# DSP_ADAU1451.net
KiCad netlist of a schematic drawn in Altium Designer
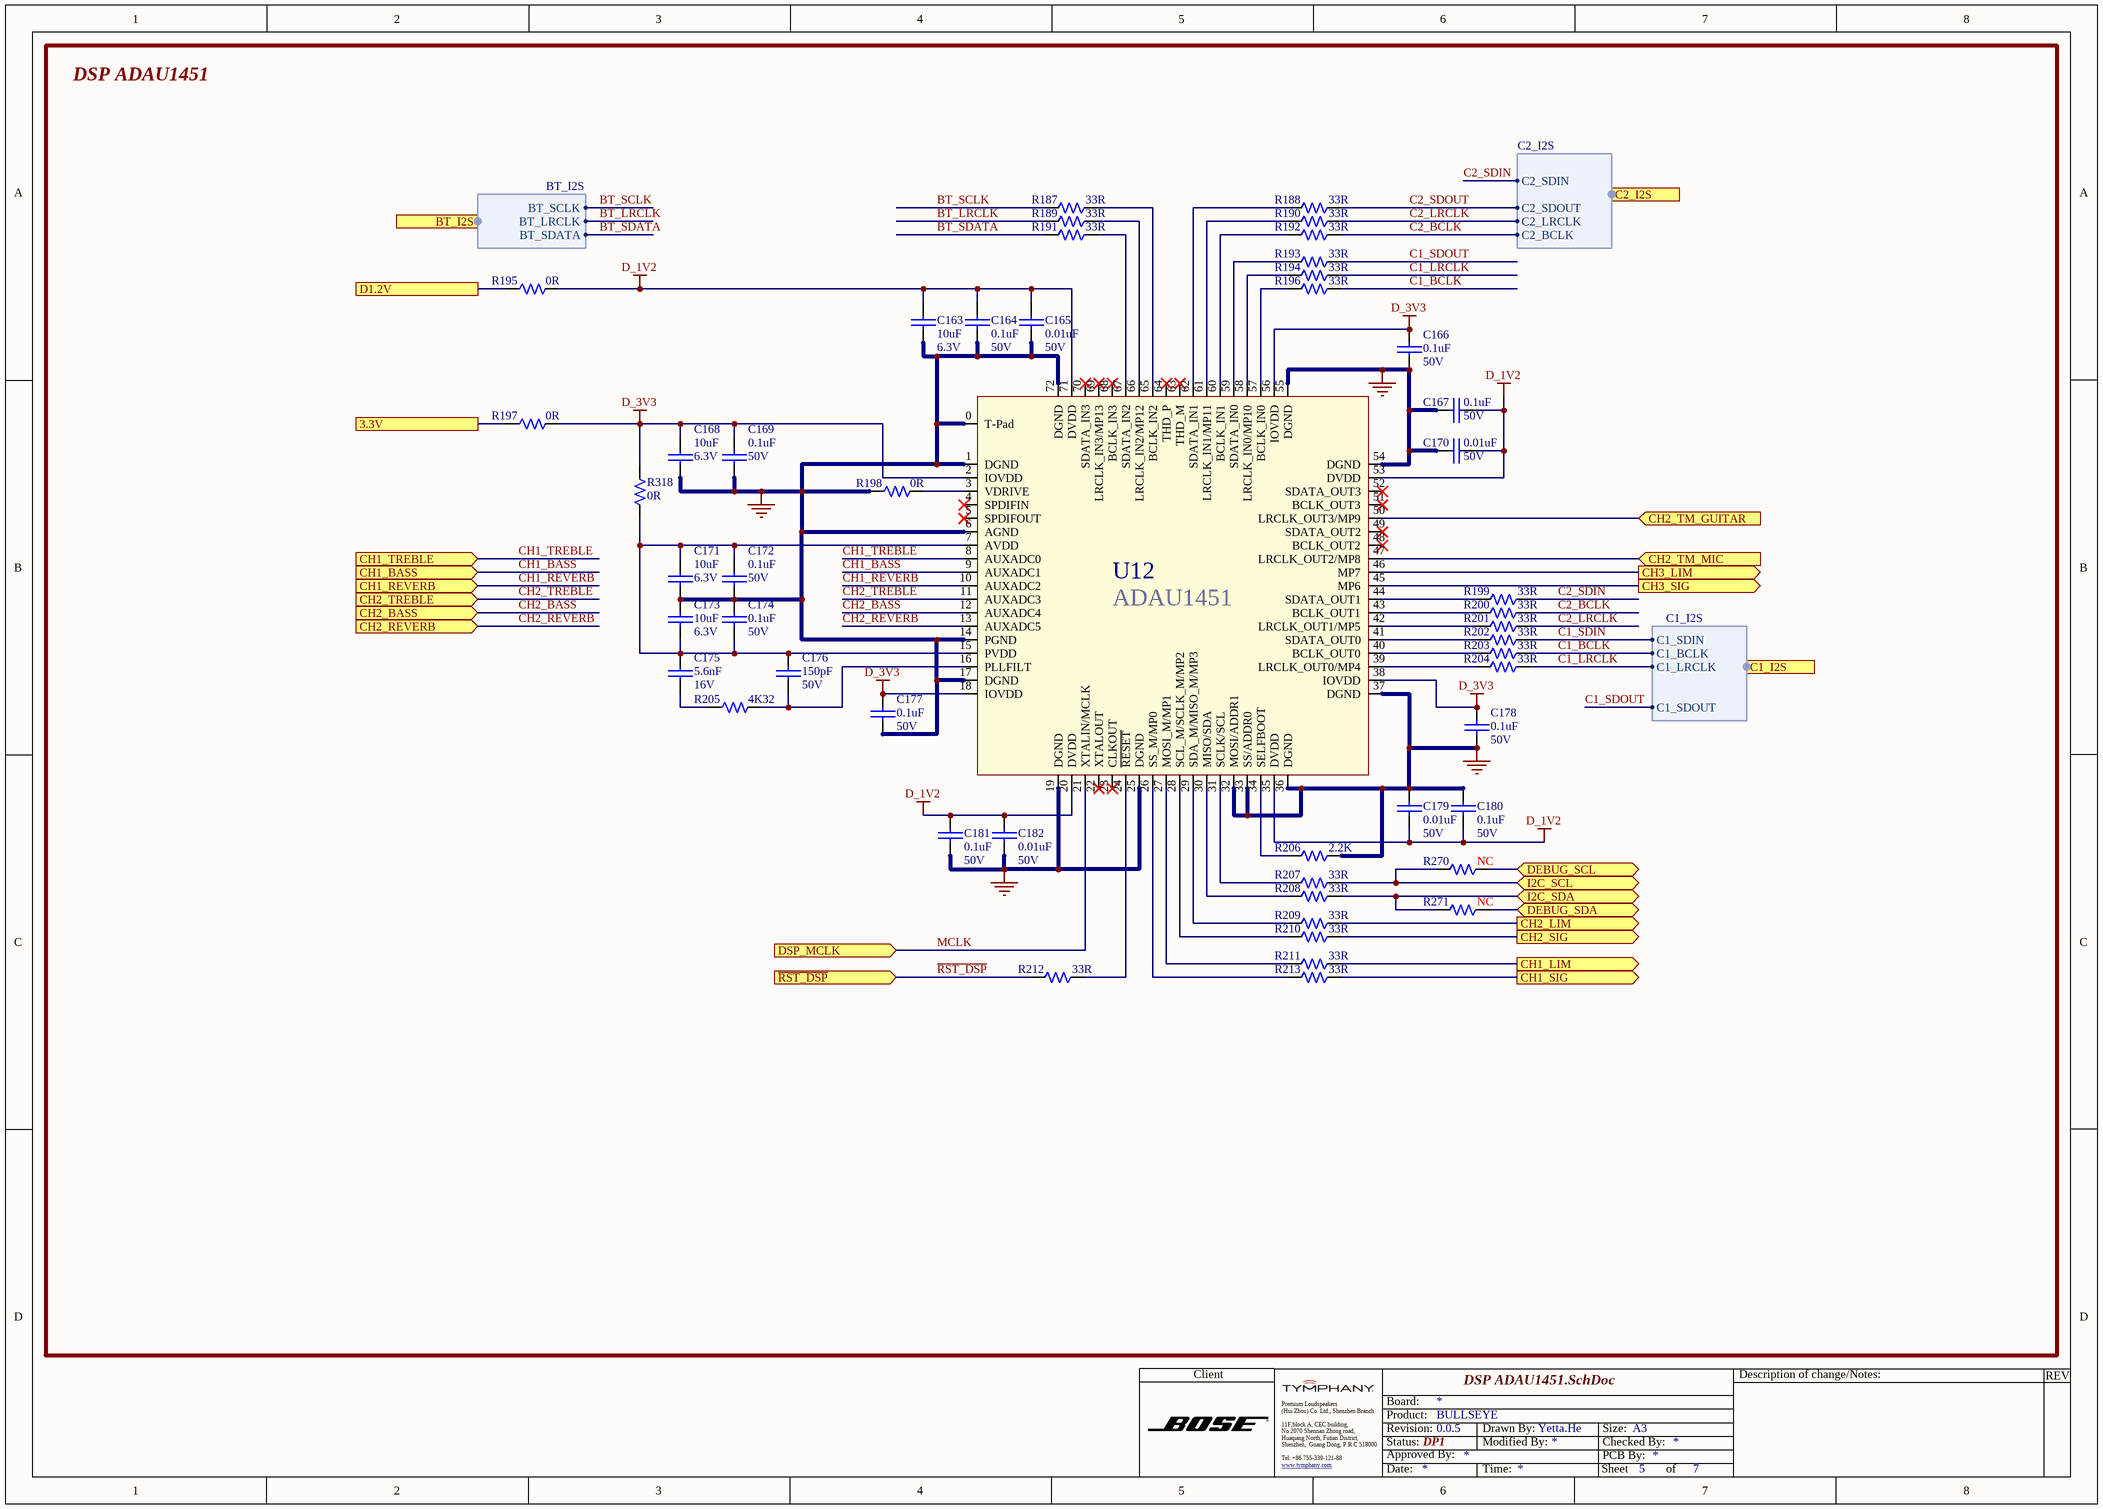
[diagram p0: DSP ADAU1451.SchDoc]

(export (version "E")
  (design (tool "Eeschema 10.0.6"))
  (components
    (comp (ref "C163")
      (value "10uF")
      (footprint "CAPC0603-RW")
      (description "CAP X5R 10UF 6.3V +-10% 0603 SAMSUN L")
      (fields
        (field (name "MFG") "SAMSUNG")
        (field (name "MFG PART") "CL10A106KQ8NNNC")
        (field (name "VOLTAGE") "6.3V")
        (field (name "CREATE_NAME") "Nathan")
      )
      (libsource (lib "P-Capacitors") (part "CAP0603 10uF 6.3V 10%_X5R_SAMSUNG"))
    )
    (comp (ref "C164")
      (value "0.1uF")
      (footprint "CAPC0402-RW")
      (description "CAP X7R .10UF 50V +-10% 0402 WALSIN L")
      (fields
        (field (name "TOLERANCE") "10%")
        (field (name "VOLTAGE") "50V")
        (field (name "Comment") "PWL456470-1040")
        (field (name "CREATE_NAME") "TOM@Deftronics")
      )
      (libsource (lib "P-Capacitors") (part "CAP0402 0.1uF 50V 10%"))
    )
    (comp (ref "C165")
      (value "0.01uF")
      (footprint "CAPC0402-RW")
      (description "CAP, CER, 0.01uF, 10%, 50V, X7R, 0402, RoHS")
      (fields
        (field (name "TOLERANCE") "10%")
        (field (name "VOLTAGE") "50V")
        (field (name "Comment") "PWL456470-1030")
        (field (name "CREATE_NAME") "Evan@Deftronics")
      )
      (libsource (lib "P-Capacitors") (part "CAP0402 0.01uF 50V 10%"))
    )
    (comp (ref "C166")
      (value "0.1uF")
      (footprint "CAPC0402-RW")
      (description "CAP X7R .10UF 50V +-10% 0402 WALSIN L")
      (fields
        (field (name "TOLERANCE") "10%")
        (field (name "VOLTAGE") "50V")
        (field (name "Comment") "PWL456470-1040")
        (field (name "CREATE_NAME") "TOM@Deftronics")
      )
      (libsource (lib "P-Capacitors") (part "CAP0402 0.1uF 50V 10%"))
    )
    (comp (ref "C167")
      (value "0.1uF")
      (footprint "CAPC0402-RW")
      (description "CAP X7R .10UF 50V +-10% 0402 WALSIN L")
      (fields
        (field (name "TOLERANCE") "10%")
        (field (name "VOLTAGE") "50V")
        (field (name "Comment") "PWL456470-1040")
        (field (name "CREATE_NAME") "TOM@Deftronics")
      )
      (libsource (lib "P-Capacitors") (part "CAP0402 0.1uF 50V 10%"))
    )
    (comp (ref "C168")
      (value "10uF")
      (footprint "CAPC0603-RW")
      (description "CAP X5R 10UF 6.3V +-10% 0603 SAMSUN L")
      (fields
        (field (name "MFG") "SAMSUNG")
        (field (name "MFG PART") "CL10A106KQ8NNNC")
        (field (name "VOLTAGE") "6.3V")
        (field (name "CREATE_NAME") "Nathan")
      )
      (libsource (lib "P-Capacitors") (part "CAP0603 10uF 6.3V 10%_X5R_SAMSUNG"))
    )
    (comp (ref "C169")
      (value "0.1uF")
      (footprint "CAPC0402-RW")
      (description "CAP X7R .10UF 50V +-10% 0402 WALSIN L")
      (fields
        (field (name "TOLERANCE") "10%")
        (field (name "VOLTAGE") "50V")
        (field (name "Comment") "PWL456470-1040")
        (field (name "CREATE_NAME") "TOM@Deftronics")
      )
      (libsource (lib "P-Capacitors") (part "CAP0402 0.1uF 50V 10%"))
    )
    (comp (ref "C170")
      (value "0.01uF")
      (footprint "CAPC0402-RW")
      (description "CAP, CER, 0.01uF, 10%, 50V, X7R, 0402, RoHS")
      (fields
        (field (name "TOLERANCE") "10%")
        (field (name "VOLTAGE") "50V")
        (field (name "Comment") "PWL456470-1030")
        (field (name "CREATE_NAME") "Evan@Deftronics")
      )
      (libsource (lib "P-Capacitors") (part "CAP0402 0.01uF 50V 10%"))
    )
    (comp (ref "C171")
      (value "10uF")
      (footprint "CAPC0603-RW")
      (description "CAP X5R 10UF 6.3V +-10% 0603 SAMSUN L")
      (fields
        (field (name "MFG") "SAMSUNG")
        (field (name "MFG PART") "CL10A106KQ8NNNC")
        (field (name "VOLTAGE") "6.3V")
        (field (name "CREATE_NAME") "Nathan")
      )
      (libsource (lib "P-Capacitors") (part "CAP0603 10uF 6.3V 10%_X5R_SAMSUNG"))
    )
    (comp (ref "C172")
      (value "0.1uF")
      (footprint "CAPC0402-RW")
      (description "CAP X7R .10UF 50V +-10% 0402 WALSIN L")
      (fields
        (field (name "TOLERANCE") "10%")
        (field (name "VOLTAGE") "50V")
        (field (name "Comment") "PWL456470-1040")
        (field (name "CREATE_NAME") "TOM@Deftronics")
      )
      (libsource (lib "P-Capacitors") (part "CAP0402 0.1uF 50V 10%"))
    )
    (comp (ref "C173")
      (value "10uF")
      (footprint "CAPC0603-RW")
      (description "CAP X5R 10UF 6.3V +-10% 0603 SAMSUN L")
      (fields
        (field (name "MFG") "SAMSUNG")
        (field (name "MFG PART") "CL10A106KQ8NNNC")
        (field (name "VOLTAGE") "6.3V")
        (field (name "CREATE_NAME") "Nathan")
      )
      (libsource (lib "P-Capacitors") (part "CAP0603 10uF 6.3V 10%_X5R_SAMSUNG"))
    )
    (comp (ref "C174")
      (value "0.1uF")
      (footprint "CAPC0402-RW")
      (description "CAP X7R .10UF 50V +-10% 0402 WALSIN L")
      (fields
        (field (name "TOLERANCE") "10%")
        (field (name "VOLTAGE") "50V")
        (field (name "Comment") "PWL456470-1040")
        (field (name "CREATE_NAME") "TOM@Deftronics")
      )
      (libsource (lib "P-Capacitors") (part "CAP0402 0.1uF 50V 10%"))
    )
    (comp (ref "C175")
      (value "5.6nF")
      (footprint "CAPC0402-RW")
      (description "CHIP CAP 10% 16V 0402 X7R  5.6nF")
      (fields (field (name "MFG") "Walsin") (field (name "TOLERANCE") "10%") (field (name "VOLTAGE") "16V"))
      (libsource (lib "P-Capacitors") (part "CAP0402 5.6nF 16V 10%"))
    )
    (comp (ref "C176")
      (value "150pF")
      (footprint "CAPC0603-RW")
      (description "CAP NPO 150PF 50V +-5% 0603 WALSIN L")
      (fields
        (field (name "MFG") "WALSIN")
        (field (name "TOLERANCE") "5%")
        (field (name "VOLTAGE") "50V")
        (field (name "CREATE_NAME") "Nathan")
      )
      (libsource (lib "P-Capacitors") (part "CAP0603 150pF 50V 5%_NPO_WALSIN"))
    )
    (comp (ref "C177")
      (value "0.1uF")
      (footprint "CAPC0402-RW")
      (description "CAP X7R .10UF 50V +-10% 0402 WALSIN L")
      (fields
        (field (name "TOLERANCE") "10%")
        (field (name "VOLTAGE") "50V")
        (field (name "Comment") "PWL456470-1040")
        (field (name "CREATE_NAME") "TOM@Deftronics")
      )
      (libsource (lib "P-Capacitors") (part "CAP0402 0.1uF 50V 10%"))
    )
    (comp (ref "C178")
      (value "0.1uF")
      (footprint "CAPC0402-RW")
      (description "CAP X7R .10UF 50V +-10% 0402 WALSIN L")
      (fields
        (field (name "TOLERANCE") "10%")
        (field (name "VOLTAGE") "50V")
        (field (name "Comment") "PWL456470-1040")
        (field (name "CREATE_NAME") "TOM@Deftronics")
      )
      (libsource (lib "P-Capacitors") (part "CAP0402 0.1uF 50V 10%"))
    )
    (comp (ref "C179")
      (value "0.01uF")
      (footprint "CAPC0402-RW")
      (description "CAP, CER, 0.01uF, 10%, 50V, X7R, 0402, RoHS")
      (fields
        (field (name "TOLERANCE") "10%")
        (field (name "VOLTAGE") "50V")
        (field (name "Comment") "PWL456470-1030")
        (field (name "CREATE_NAME") "Evan@Deftronics")
      )
      (libsource (lib "P-Capacitors") (part "CAP0402 0.01uF 50V 10%"))
    )
    (comp (ref "C180")
      (value "0.1uF")
      (footprint "CAPC0402-RW")
      (description "CAP X7R .10UF 50V +-10% 0402 WALSIN L")
      (fields
        (field (name "TOLERANCE") "10%")
        (field (name "VOLTAGE") "50V")
        (field (name "Comment") "PWL456470-1040")
        (field (name "CREATE_NAME") "TOM@Deftronics")
      )
      (libsource (lib "P-Capacitors") (part "CAP0402 0.1uF 50V 10%"))
    )
    (comp (ref "C181")
      (value "0.1uF")
      (footprint "CAPC0402-RW")
      (description "CAP X7R .10UF 50V +-10% 0402 WALSIN L")
      (fields
        (field (name "TOLERANCE") "10%")
        (field (name "VOLTAGE") "50V")
        (field (name "Comment") "PWL456470-1040")
        (field (name "CREATE_NAME") "TOM@Deftronics")
      )
      (libsource (lib "P-Capacitors") (part "CAP0402 0.1uF 50V 10%"))
    )
    (comp (ref "C182")
      (value "0.01uF")
      (footprint "CAPC0402-RW")
      (description "CAP, CER, 0.01uF, 10%, 50V, X7R, 0402, RoHS")
      (fields
        (field (name "TOLERANCE") "10%")
        (field (name "VOLTAGE") "50V")
        (field (name "Comment") "PWL456470-1030")
        (field (name "CREATE_NAME") "Evan@Deftronics")
      )
      (libsource (lib "P-Capacitors") (part "CAP0402 0.01uF 50V 10%"))
    )
    (comp (ref "R187")
      (value "33R")
      (footprint "0402-RW")
      (description "CHIP RES 33 OHM 1/16W 1% 0402")
      (fields (field (name "POWER") "1/16W") (field (name "MFG") "WALSIN"))
      (libsource (lib "Q-Resistors") (part "RES0402 1/16W 1% 33 OHM"))
    )
    (comp (ref "R188")
      (value "33R")
      (footprint "0402-RW")
      (description "CHIP RES 33 OHM 1/16W 1% 0402")
      (fields (field (name "POWER") "1/16W") (field (name "MFG") "WALSIN"))
      (libsource (lib "Q-Resistors") (part "RES0402 1/16W 1% 33 OHM"))
    )
    (comp (ref "R189")
      (value "33R")
      (footprint "0402-RW")
      (description "CHIP RES 33 OHM 1/16W 1% 0402")
      (fields (field (name "POWER") "1/16W") (field (name "MFG") "WALSIN"))
      (libsource (lib "Q-Resistors") (part "RES0402 1/16W 1% 33 OHM"))
    )
    (comp (ref "R190")
      (value "33R")
      (footprint "0402-RW")
      (description "CHIP RES 33 OHM 1/16W 1% 0402")
      (fields (field (name "POWER") "1/16W") (field (name "MFG") "WALSIN"))
      (libsource (lib "Q-Resistors") (part "RES0402 1/16W 1% 33 OHM"))
    )
    (comp (ref "R191")
      (value "33R")
      (footprint "0402-RW")
      (description "CHIP RES 33 OHM 1/16W 1% 0402")
      (fields (field (name "POWER") "1/16W") (field (name "MFG") "WALSIN"))
      (libsource (lib "Q-Resistors") (part "RES0402 1/16W 1% 33 OHM"))
    )
    (comp (ref "R192")
      (value "33R")
      (footprint "0402-RW")
      (description "CHIP RES 33 OHM 1/16W 1% 0402")
      (fields (field (name "POWER") "1/16W") (field (name "MFG") "WALSIN"))
      (libsource (lib "Q-Resistors") (part "RES0402 1/16W 1% 33 OHM"))
    )
    (comp (ref "R193")
      (value "33R")
      (footprint "0402-RW")
      (description "CHIP RES 33 OHM 1/16W 1% 0402")
      (fields (field (name "POWER") "1/16W") (field (name "MFG") "WALSIN"))
      (libsource (lib "Q-Resistors") (part "RES0402 1/16W 1% 33 OHM"))
    )
    (comp (ref "R194")
      (value "33R")
      (footprint "0402-RW")
      (description "CHIP RES 33 OHM 1/16W 1% 0402")
      (fields (field (name "POWER") "1/16W") (field (name "MFG") "WALSIN"))
      (libsource (lib "Q-Resistors") (part "RES0402 1/16W 1% 33 OHM"))
    )
    (comp (ref "R195")
      (value "0R")
      (footprint "0603-RW")
      (description "CHIP 0 OHM 0 OHM 0 OHM 0603 WALSIN L")
      (fields (field (name "POWER") "1/10W") (field (name "MFG PART") "WR06X000PTL"))
      (libsource (lib "Q-Resistors") (part "RES0603 1/10W 0 OHM_WALSIN"))
    )
    (comp (ref "R196")
      (value "33R")
      (footprint "0402-RW")
      (description "CHIP RES 33 OHM 1/16W 1% 0402")
      (fields (field (name "POWER") "1/16W") (field (name "MFG") "WALSIN"))
      (libsource (lib "Q-Resistors") (part "RES0402 1/16W 1% 33 OHM"))
    )
    (comp (ref "R197")
      (value "0R")
      (footprint "0603-RW")
      (description "CHIP 0 OHM 0 OHM 0 OHM 0603 WALSIN L")
      (fields (field (name "POWER") "1/10W") (field (name "MFG PART") "WR06X000PTL"))
      (libsource (lib "Q-Resistors") (part "RES0603 1/10W 0 OHM_WALSIN"))
    )
    (comp (ref "R198")
      (value "0R")
      (footprint "0603-RW")
      (description "CHIP 0 OHM 0 OHM 0 OHM 0603 WALSIN L")
      (fields (field (name "POWER") "1/10W") (field (name "MFG PART") "WR06X000PTL"))
      (libsource (lib "Q-Resistors") (part "RES0603 1/10W 0 OHM_WALSIN"))
    )
    (comp (ref "R199")
      (value "33R")
      (footprint "0402-RW")
      (description "CHIP RES 33 OHM 1/16W 1% 0402")
      (fields (field (name "POWER") "1/16W") (field (name "MFG") "WALSIN"))
      (libsource (lib "Q-Resistors") (part "RES0402 1/16W 1% 33 OHM"))
    )
    (comp (ref "R200")
      (value "33R")
      (footprint "0402-RW")
      (description "CHIP RES 33 OHM 1/16W 1% 0402")
      (fields (field (name "POWER") "1/16W") (field (name "MFG") "WALSIN"))
      (libsource (lib "Q-Resistors") (part "RES0402 1/16W 1% 33 OHM"))
    )
    (comp (ref "R201")
      (value "33R")
      (footprint "0402-RW")
      (description "CHIP RES 33 OHM 1/16W 1% 0402")
      (fields (field (name "POWER") "1/16W") (field (name "MFG") "WALSIN"))
      (libsource (lib "Q-Resistors") (part "RES0402 1/16W 1% 33 OHM"))
    )
    (comp (ref "R202")
      (value "33R")
      (footprint "0402-RW")
      (description "CHIP RES 33 OHM 1/16W 1% 0402")
      (fields (field (name "POWER") "1/16W") (field (name "MFG") "WALSIN"))
      (libsource (lib "Q-Resistors") (part "RES0402 1/16W 1% 33 OHM"))
    )
    (comp (ref "R203")
      (value "33R")
      (footprint "0402-RW")
      (description "CHIP RES 33 OHM 1/16W 1% 0402")
      (fields (field (name "POWER") "1/16W") (field (name "MFG") "WALSIN"))
      (libsource (lib "Q-Resistors") (part "RES0402 1/16W 1% 33 OHM"))
    )
    (comp (ref "R204")
      (value "33R")
      (footprint "0402-RW")
      (description "CHIP RES 33 OHM 1/16W 1% 0402")
      (fields (field (name "POWER") "1/16W") (field (name "MFG") "WALSIN"))
      (libsource (lib "Q-Resistors") (part "RES0402 1/16W 1% 33 OHM"))
    )
    (comp (ref "R205")
      (value "4K32")
      (footprint "0402-RW")
      (description "CHIP 4.32K OHM 100PPM +-1% 0402 WALS L")
      (fields
        (field (name "MFG") "WALSIN (華新)")
        (field (name "POWER") "1/16W")
        (field (name "CREATE_NAME") "Nathan")
      )
      (libsource (lib "Q-Resistors") (part "RES0402 1/16W 1% 4.32K OMH_WALSIN"))
    )
    (comp (ref "R206")
      (value "2.2K")
      (footprint "0603-RW")
      (description "GP CHIP RES. 2.2K OHM 1/10W 1% 0603")
      (fields (field (name "POWER") "1/10W") (field (name "Comment") "QCF011030-2201"))
      (libsource (lib "Q-Resistors") (part "RES0603 1/10W 1% 2.2K OHM"))
    )
    (comp (ref "R207")
      (value "33R")
      (footprint "0402-RW")
      (description "CHIP RES 33 OHM 1/16W 1% 0402")
      (fields (field (name "POWER") "1/16W") (field (name "MFG") "WALSIN"))
      (libsource (lib "Q-Resistors") (part "RES0402 1/16W 1% 33 OHM"))
    )
    (comp (ref "R208")
      (value "33R")
      (footprint "0402-RW")
      (description "CHIP RES 33 OHM 1/16W 1% 0402")
      (fields (field (name "POWER") "1/16W") (field (name "MFG") "WALSIN"))
      (libsource (lib "Q-Resistors") (part "RES0402 1/16W 1% 33 OHM"))
    )
    (comp (ref "R209")
      (value "33R")
      (footprint "0402-RW")
      (description "CHIP RES 33 OHM 1/16W 1% 0402")
      (fields (field (name "POWER") "1/16W") (field (name "MFG") "WALSIN"))
      (libsource (lib "Q-Resistors") (part "RES0402 1/16W 1% 33 OHM"))
    )
    (comp (ref "R210")
      (value "33R")
      (footprint "0402-RW")
      (description "CHIP RES 33 OHM 1/16W 1% 0402")
      (fields (field (name "POWER") "1/16W") (field (name "MFG") "WALSIN"))
      (libsource (lib "Q-Resistors") (part "RES0402 1/16W 1% 33 OHM"))
    )
    (comp (ref "R211")
      (value "33R")
      (footprint "0402-RW")
      (description "CHIP RES 33 OHM 1/16W 1% 0402")
      (fields (field (name "POWER") "1/16W") (field (name "MFG") "WALSIN"))
      (libsource (lib "Q-Resistors") (part "RES0402 1/16W 1% 33 OHM"))
    )
    (comp (ref "R212")
      (value "33R")
      (footprint "0402-RW")
      (description "CHIP RES 33 OHM 1/16W 1% 0402")
      (fields (field (name "POWER") "1/16W") (field (name "MFG") "WALSIN"))
      (libsource (lib "Q-Resistors") (part "RES0402 1/16W 1% 33 OHM"))
    )
    (comp (ref "R213")
      (value "33R")
      (footprint "0402-RW")
      (description "CHIP RES 33 OHM 1/16W 1% 0402")
      (fields (field (name "POWER") "1/16W") (field (name "MFG") "WALSIN"))
      (libsource (lib "Q-Resistors") (part "RES0402 1/16W 1% 33 OHM"))
    )
    (comp (ref "R270")
      (value "NC")
      (footprint "0603-RW")
      (fields (field (name "Comment") "RES0603 NC") (field (name "CREATE_NAME") "Tom"))
      (libsource (lib "Temporary") (part "RES0603 NC"))
    )
    (comp (ref "R271")
      (value "NC")
      (footprint "0603-RW")
      (fields (field (name "Comment") "RES0603 NC") (field (name "CREATE_NAME") "Tom"))
      (libsource (lib "Temporary") (part "RES0603 NC"))
    )
    (comp (ref "R318")
      (value "0R")
      (footprint "0603-RW")
      (description "CHIP 0 OHM 0 OHM 0 OHM 0603 WALSIN L")
      (fields (field (name "POWER") "1/10W") (field (name "MFG PART") "WR06X000PTL"))
      (libsource (lib "Q-Resistors") (part "RES0603 1/10W 0 OHM_WALSIN"))
    )
    (comp (ref "U12")
      (value "T610000050936")
      (footprint "QFN50P1000X1000X100-72N")
      (description "SP ADAU1451 LFCSP-72 ADI (AN K")
      (fields
        (field (name "MFG") "ADI (ANALOG DEVICES)")
        (field (name "MFG PART") "ADAU1451")
        (field (name "CREATE_NAME") "Tom")
      )
      (libsource (lib "R-Semiconductors") (part "ADAU1451"))
    )
  )
  (nets
    (net (code "4") (name "/3.3V") (class "Default")
      (node (ref "R197") (pin "1") (pinfunction "1_1") (pintype "passive"))
    )
    (net (code "5") (name "/BT_LRCLK") (class "Default")
      (node (ref "R189") (pin "2") (pinfunction "2_2") (pintype "passive"))
    )
    (net (code "6") (name "/BT_SCLK") (class "Default")
      (node (ref "R187") (pin "2") (pinfunction "2_2") (pintype "passive"))
    )
    (net (code "7") (name "/BT_SDATA") (class "Default")
      (node (ref "R191") (pin "2") (pinfunction "2_2") (pintype "passive"))
    )
    (net (code "8") (name "/C1_BCLK") (class "Default")
      (node (ref "R196") (pin "1") (pinfunction "1_1") (pintype "passive"))
      (node (ref "R203") (pin "1") (pinfunction "1_1") (pintype "passive"))
    )
    (net (code "9") (name "/C1_LRCLK") (class "Default")
      (node (ref "R194") (pin "1") (pinfunction "1_1") (pintype "passive"))
      (node (ref "R204") (pin "1") (pinfunction "1_1") (pintype "passive"))
    )
    (net (code "10") (name "/C1_SDIN") (class "Default")
      (node (ref "R202") (pin "1") (pinfunction "1_1") (pintype "passive"))
    )
    (net (code "11") (name "/C1_SDOUT") (class "Default")
      (node (ref "R193") (pin "1") (pinfunction "1_1") (pintype "passive"))
    )
    (net (code "12") (name "/C2_BCLK") (class "Default")
      (node (ref "R192") (pin "1") (pinfunction "1_1") (pintype "passive"))
      (node (ref "R200") (pin "1") (pinfunction "1_1") (pintype "passive"))
    )
    (net (code "13") (name "/C2_LRCLK") (class "Default")
      (node (ref "R190") (pin "1") (pinfunction "1_1") (pintype "passive"))
      (node (ref "R201") (pin "1") (pinfunction "1_1") (pintype "passive"))
    )
    (net (code "14") (name "/C2_SDIN") (class "Default")
      (node (ref "R199") (pin "1") (pinfunction "1_1") (pintype "passive"))
    )
    (net (code "15") (name "/C2_SDOUT") (class "Default")
      (node (ref "R188") (pin "1") (pinfunction "1_1") (pintype "passive"))
    )
    (net (code "16") (name "/CH1_BASS") (class "Default")
      (node (ref "U12") (pin "9") (pinfunction "AUXADC1_9") (pintype "passive"))
    )
    (net (code "17") (name "/CH1_LIM") (class "Default")
      (node (ref "R211") (pin "1") (pinfunction "1_1") (pintype "passive"))
    )
    (net (code "18") (name "/CH1_REVERB") (class "Default")
      (node (ref "U12") (pin "10") (pinfunction "AUXADC2_10") (pintype "passive"))
    )
    (net (code "19") (name "/CH1_SIG") (class "Default")
      (node (ref "R213") (pin "1") (pinfunction "1_1") (pintype "passive"))
    )
    (net (code "20") (name "/CH1_TREBLE") (class "Default")
      (node (ref "U12") (pin "8") (pinfunction "AUXADC0_8") (pintype "passive"))
    )
    (net (code "21") (name "/CH2_BASS") (class "Default")
      (node (ref "U12") (pin "12") (pinfunction "AUXADC4_12") (pintype "passive"))
    )
    (net (code "22") (name "/CH2_LIM") (class "Default")
      (node (ref "R209") (pin "1") (pinfunction "1_1") (pintype "passive"))
    )
    (net (code "23") (name "/CH2_REVERB") (class "Default")
      (node (ref "U12") (pin "13") (pinfunction "AUXADC5_13") (pintype "passive"))
    )
    (net (code "24") (name "/CH2_SIG") (class "Default")
      (node (ref "R210") (pin "1") (pinfunction "1_1") (pintype "passive"))
    )
    (net (code "25") (name "/CH2_TM_GUITAR") (class "Default")
      (node (ref "U12") (pin "50") (pinfunction "LRCLK_OUT3/MP9_50") (pintype "passive"))
    )
    (net (code "26") (name "/CH2_TM_MIC") (class "Default")
      (node (ref "U12") (pin "47") (pinfunction "LRCLK_OUT2/MP8_47") (pintype "passive"))
    )
    (net (code "27") (name "/CH2_TREBLE") (class "Default")
      (node (ref "U12") (pin "11") (pinfunction "AUXADC3_11") (pintype "passive"))
    )
    (net (code "28") (name "/CH3_LIM") (class "Default")
      (node (ref "U12") (pin "46") (pinfunction "MP7_46") (pintype "passive"))
    )
    (net (code "29") (name "/CH3_SIG") (class "Default")
      (node (ref "U12") (pin "45") (pinfunction "MP6_45") (pintype "passive"))
    )
    (net (code "30") (name "/D1.2V") (class "Default")
      (node (ref "R195") (pin "1") (pinfunction "1_1") (pintype "passive"))
    )
    (net (code "31") (name "/DEBUG_SCL") (class "Default")
      (node (ref "R270") (pin "1") (pinfunction "1_1") (pintype "passive"))
    )
    (net (code "32") (name "/DEBUG_SDA") (class "Default")
      (node (ref "R271") (pin "1") (pinfunction "1_1") (pintype "passive"))
    )
    (net (code "33") (name "/I2C_SCL") (class "Default")
      (node (ref "R207") (pin "1") (pinfunction "1_1") (pintype "passive"))
      (node (ref "R270") (pin "2") (pinfunction "2_2") (pintype "passive"))
    )
    (net (code "34") (name "/I2C_SDA") (class "Default")
      (node (ref "R208") (pin "1") (pinfunction "1_1") (pintype "passive"))
      (node (ref "R271") (pin "2") (pinfunction "2_2") (pintype "passive"))
    )
    (net (code "35") (name "/MCLK") (class "Default")
      (node (ref "U12") (pin "21") (pinfunction "XTALIN/MCLK_21") (pintype "passive"))
    )
    (net (code "39") (name "/~{RST_DSP}") (class "Default")
      (node (ref "R212") (pin "2") (pinfunction "2_2") (pintype "passive"))
    )
    (net (code "40") (name "D_1V2") (class "Default")
      (node (ref "C163") (pin "1") (pinfunction "1_1") (pintype "passive"))
      (node (ref "C164") (pin "1") (pinfunction "1_1") (pintype "passive"))
      (node (ref "C165") (pin "1") (pinfunction "1_1") (pintype "passive"))
      (node (ref "C167") (pin "2") (pinfunction "2_2") (pintype "passive"))
      (node (ref "C170") (pin "2") (pinfunction "2_2") (pintype "passive"))
      (node (ref "C179") (pin "2") (pinfunction "2_2") (pintype "passive"))
      (node (ref "C180") (pin "2") (pinfunction "2_2") (pintype "passive"))
      (node (ref "C181") (pin "1") (pinfunction "1_1") (pintype "passive"))
      (node (ref "C182") (pin "1") (pinfunction "1_1") (pintype "passive"))
      (node (ref "R195") (pin "2") (pinfunction "2_2") (pintype "passive"))
      (node (ref "U12") (pin "20") (pinfunction "DVDD_20") (pintype "passive"))
      (node (ref "U12") (pin "35") (pinfunction "DVDD_35") (pintype "passive"))
      (node (ref "U12") (pin "53") (pinfunction "DVDD_53") (pintype "passive"))
      (node (ref "U12") (pin "71") (pinfunction "DVDD_71") (pintype "passive"))
    )
    (net (code "41") (name "D_3V3") (class "Default")
      (node (ref "C166") (pin "1") (pinfunction "1_1") (pintype "passive"))
      (node (ref "C168") (pin "1") (pinfunction "1_1") (pintype "passive"))
      (node (ref "C169") (pin "1") (pinfunction "1_1") (pintype "passive"))
      (node (ref "C177") (pin "1") (pinfunction "1_1") (pintype "passive"))
      (node (ref "C178") (pin "1") (pinfunction "1_1") (pintype "passive"))
      (node (ref "R197") (pin "2") (pinfunction "2_2") (pintype "passive"))
      (node (ref "R318") (pin "1") (pinfunction "1_1") (pintype "passive"))
      (node (ref "U12") (pin "18") (pinfunction "IOVDD_18") (pintype "passive"))
      (node (ref "U12") (pin "2") (pinfunction "IOVDD_2") (pintype "passive"))
      (node (ref "U12") (pin "38") (pinfunction "IOVDD_38") (pintype "passive"))
      (node (ref "U12") (pin "56") (pinfunction "IOVDD_56") (pintype "passive"))
    )
    (net (code "42") (name "GND") (class "Default")
      (node (ref "C163") (pin "2") (pinfunction "2_2") (pintype "passive"))
      (node (ref "C164") (pin "2") (pinfunction "2_2") (pintype "passive"))
      (node (ref "C165") (pin "2") (pinfunction "2_2") (pintype "passive"))
      (node (ref "C166") (pin "2") (pinfunction "2_2") (pintype "passive"))
      (node (ref "C167") (pin "1") (pinfunction "1_1") (pintype "passive"))
      (node (ref "C168") (pin "2") (pinfunction "2_2") (pintype "passive"))
      (node (ref "C169") (pin "2") (pinfunction "2_2") (pintype "passive"))
      (node (ref "C170") (pin "1") (pinfunction "1_1") (pintype "passive"))
      (node (ref "C171") (pin "2") (pinfunction "2_2") (pintype "passive"))
      (node (ref "C172") (pin "2") (pinfunction "2_2") (pintype "passive"))
      (node (ref "C173") (pin "1") (pinfunction "1_1") (pintype "passive"))
      (node (ref "C174") (pin "1") (pinfunction "1_1") (pintype "passive"))
      (node (ref "C177") (pin "2") (pinfunction "2_2") (pintype "passive"))
      (node (ref "C178") (pin "2") (pinfunction "2_2") (pintype "passive"))
      (node (ref "C179") (pin "1") (pinfunction "1_1") (pintype "passive"))
      (node (ref "C180") (pin "1") (pinfunction "1_1") (pintype "passive"))
      (node (ref "C181") (pin "2") (pinfunction "2_2") (pintype "passive"))
      (node (ref "C182") (pin "2") (pinfunction "2_2") (pintype "passive"))
      (node (ref "R198") (pin "1") (pinfunction "1_1") (pintype "passive"))
      (node (ref "R206") (pin "1") (pinfunction "1_1") (pintype "passive"))
      (node (ref "U12") (pin "0") (pinfunction "T-Pad_0") (pintype "passive"))
      (node (ref "U12") (pin "1") (pinfunction "DGND_1") (pintype "passive"))
      (node (ref "U12") (pin "14") (pinfunction "PGND_14") (pintype "passive"))
      (node (ref "U12") (pin "17") (pinfunction "DGND_17") (pintype "passive"))
      (node (ref "U12") (pin "19") (pinfunction "DGND_19") (pintype "passive"))
      (node (ref "U12") (pin "25") (pinfunction "DGND_25") (pintype "passive"))
      (node (ref "U12") (pin "32") (pinfunction "MOSI/ADDR1_32") (pintype "passive"))
      (node (ref "U12") (pin "33") (pinfunction "SS/ADDR0_33") (pintype "passive"))
      (node (ref "U12") (pin "36") (pinfunction "DGND_36") (pintype "passive"))
      (node (ref "U12") (pin "37") (pinfunction "DGND_37") (pintype "passive"))
      (node (ref "U12") (pin "54") (pinfunction "DGND_54") (pintype "passive"))
      (node (ref "U12") (pin "55") (pinfunction "DGND_55") (pintype "passive"))
      (node (ref "U12") (pin "6") (pinfunction "AGND_6") (pintype "passive"))
      (node (ref "U12") (pin "72") (pinfunction "DGND_72") (pintype "passive"))
    )
    (net (code "43") (name "Net-(C175-Pad2)") (class "Default")
      (node (ref "C175") (pin "2") (pinfunction "2_2") (pintype "passive"))
      (node (ref "R205") (pin "1") (pinfunction "1_1") (pintype "passive"))
    )
    (net (code "44") (name "Net-(U12-AVDD)") (class "Default")
      (node (ref "C171") (pin "1") (pinfunction "1_1") (pintype "passive"))
      (node (ref "C172") (pin "1") (pinfunction "1_1") (pintype "passive"))
      (node (ref "C173") (pin "2") (pinfunction "2_2") (pintype "passive"))
      (node (ref "C174") (pin "2") (pinfunction "2_2") (pintype "passive"))
      (node (ref "C175") (pin "1") (pinfunction "1_1") (pintype "passive"))
      (node (ref "C176") (pin "1") (pinfunction "1_1") (pintype "passive"))
      (node (ref "R318") (pin "2") (pinfunction "2_2") (pintype "passive"))
      (node (ref "U12") (pin "15") (pinfunction "PVDD_15") (pintype "passive"))
      (node (ref "U12") (pin "7") (pinfunction "AVDD_7") (pintype "passive"))
    )
    (net (code "45") (name "Net-(U12-BCLK_IN0)") (class "Default")
      (node (ref "R196") (pin "2") (pinfunction "2_2") (pintype "passive"))
      (node (ref "U12") (pin "57") (pinfunction "BCLK_IN0_57") (pintype "passive"))
    )
    (net (code "46") (name "Net-(U12-BCLK_IN1)") (class "Default")
      (node (ref "R192") (pin "2") (pinfunction "2_2") (pintype "passive"))
      (node (ref "U12") (pin "60") (pinfunction "BCLK_IN1_60") (pintype "passive"))
    )
    (net (code "47") (name "Net-(U12-BCLK_IN2)") (class "Default")
      (node (ref "R187") (pin "1") (pinfunction "1_1") (pintype "passive"))
      (node (ref "U12") (pin "65") (pinfunction "BCLK_IN2_65") (pintype "passive"))
    )
    (net (code "48") (name "Net-(U12-BCLK_OUT0)") (class "Default")
      (node (ref "R203") (pin "2") (pinfunction "2_2") (pintype "passive"))
      (node (ref "U12") (pin "40") (pinfunction "BCLK_OUT0_40") (pintype "passive"))
    )
    (net (code "49") (name "Net-(U12-BCLK_OUT1)") (class "Default")
      (node (ref "R200") (pin "2") (pinfunction "2_2") (pintype "passive"))
      (node (ref "U12") (pin "43") (pinfunction "BCLK_OUT1_43") (pintype "passive"))
    )
    (net (code "50") (name "Net-(U12-LRCLK_IN0{slash}MP10)") (class "Default")
      (node (ref "R194") (pin "2") (pinfunction "2_2") (pintype "passive"))
      (node (ref "U12") (pin "58") (pinfunction "LRCLK_IN0/MP10_58") (pintype "passive"))
    )
    (net (code "51") (name "Net-(U12-LRCLK_IN1{slash}MP11)") (class "Default")
      (node (ref "R190") (pin "2") (pinfunction "2_2") (pintype "passive"))
      (node (ref "U12") (pin "61") (pinfunction "LRCLK_IN1/MP11_61") (pintype "passive"))
    )
    (net (code "52") (name "Net-(U12-LRCLK_IN2{slash}MP12)") (class "Default")
      (node (ref "R189") (pin "1") (pinfunction "1_1") (pintype "passive"))
      (node (ref "U12") (pin "66") (pinfunction "LRCLK_IN2/MP12_66") (pintype "passive"))
    )
    (net (code "53") (name "Net-(U12-LRCLK_OUT0{slash}MP4)") (class "Default")
      (node (ref "R204") (pin "2") (pinfunction "2_2") (pintype "passive"))
      (node (ref "U12") (pin "39") (pinfunction "LRCLK_OUT0/MP4_39") (pintype "passive"))
    )
    (net (code "54") (name "Net-(U12-LRCLK_OUT1{slash}MP5)") (class "Default")
      (node (ref "R201") (pin "2") (pinfunction "2_2") (pintype "passive"))
      (node (ref "U12") (pin "42") (pinfunction "LRCLK_OUT1/MP5_42") (pintype "passive"))
    )
    (net (code "55") (name "Net-(U12-MISO{slash}SDA)") (class "Default")
      (node (ref "R208") (pin "2") (pinfunction "2_2") (pintype "passive"))
      (node (ref "U12") (pin "30") (pinfunction "MISO/SDA_30") (pintype "passive"))
    )
    (net (code "56") (name "Net-(U12-MOSI_M{slash}MP1)") (class "Default")
      (node (ref "R211") (pin "2") (pinfunction "2_2") (pintype "passive"))
      (node (ref "U12") (pin "27") (pinfunction "MOSI_M/MP1_27") (pintype "passive"))
    )
    (net (code "57") (name "Net-(U12-PLLFILT)") (class "Default")
      (node (ref "C176") (pin "2") (pinfunction "2_2") (pintype "passive"))
      (node (ref "R205") (pin "2") (pinfunction "2_2") (pintype "passive"))
      (node (ref "U12") (pin "16") (pinfunction "PLLFILT_16") (pintype "passive"))
    )
    (net (code "58") (name "Net-(U12-SCLK{slash}SCL)") (class "Default")
      (node (ref "R207") (pin "2") (pinfunction "2_2") (pintype "passive"))
      (node (ref "U12") (pin "31") (pinfunction "SCLK/SCL_31") (pintype "passive"))
    )
    (net (code "59") (name "Net-(U12-SCL_M{slash}SCLK_M{slash}MP2)") (class "Default")
      (node (ref "R210") (pin "2") (pinfunction "2_2") (pintype "passive"))
      (node (ref "U12") (pin "28") (pinfunction "SCL_M/SCLK_M/MP2_28") (pintype "passive"))
    )
    (net (code "60") (name "Net-(U12-SDATA_IN0)") (class "Default")
      (node (ref "R193") (pin "2") (pinfunction "2_2") (pintype "passive"))
      (node (ref "U12") (pin "59") (pinfunction "SDATA_IN0_59") (pintype "passive"))
    )
    (net (code "61") (name "Net-(U12-SDATA_IN1)") (class "Default")
      (node (ref "R188") (pin "2") (pinfunction "2_2") (pintype "passive"))
      (node (ref "U12") (pin "62") (pinfunction "SDATA_IN1_62") (pintype "passive"))
    )
    (net (code "62") (name "Net-(U12-SDATA_IN2)") (class "Default")
      (node (ref "R191") (pin "1") (pinfunction "1_1") (pintype "passive"))
      (node (ref "U12") (pin "67") (pinfunction "SDATA_IN2_67") (pintype "passive"))
    )
    (net (code "63") (name "Net-(U12-SDATA_OUT0)") (class "Default")
      (node (ref "R202") (pin "2") (pinfunction "2_2") (pintype "passive"))
      (node (ref "U12") (pin "41") (pinfunction "SDATA_OUT0_41") (pintype "passive"))
    )
    (net (code "64") (name "Net-(U12-SDATA_OUT1)") (class "Default")
      (node (ref "R199") (pin "2") (pinfunction "2_2") (pintype "passive"))
      (node (ref "U12") (pin "44") (pinfunction "SDATA_OUT1_44") (pintype "passive"))
    )
    (net (code "65") (name "Net-(U12-SDA_M{slash}MISO_M{slash}MP3)") (class "Default")
      (node (ref "R209") (pin "2") (pinfunction "2_2") (pintype "passive"))
      (node (ref "U12") (pin "29") (pinfunction "SDA_M/MISO_M/MP3_29") (pintype "passive"))
    )
    (net (code "66") (name "Net-(U12-SELFBOOT)") (class "Default")
      (node (ref "R206") (pin "2") (pinfunction "2_2") (pintype "passive"))
      (node (ref "U12") (pin "34") (pinfunction "SELFBOOT_34") (pintype "passive"))
    )
    (net (code "67") (name "Net-(U12-SS_M{slash}MP0)") (class "Default")
      (node (ref "R213") (pin "2") (pinfunction "2_2") (pintype "passive"))
      (node (ref "U12") (pin "26") (pinfunction "SS_M/MP0_26") (pintype "passive"))
    )
    (net (code "68") (name "Net-(U12-VDRIVE)") (class "Default")
      (node (ref "R198") (pin "2") (pinfunction "2_2") (pintype "passive"))
      (node (ref "U12") (pin "3") (pinfunction "VDRIVE_3") (pintype "passive"))
    )
    (net (code "69") (name "Net-(U12-~{RESET})") (class "Default")
      (node (ref "R212") (pin "1") (pinfunction "1_1") (pintype "passive"))
      (node (ref "U12") (pin "24") (pinfunction "~{RESET}_24") (pintype "passive"))
    )
    (net (code "70") (name "unconnected-(U12-BCLK_IN3-Pad68)") (class "Default")
      (node (ref "U12") (pin "68") (pinfunction "BCLK_IN3_68") (pintype "passive+no_connect"))
    )
    (net (code "71") (name "unconnected-(U12-BCLK_OUT2-Pad48)") (class "Default")
      (node (ref "U12") (pin "48") (pinfunction "BCLK_OUT2_48") (pintype "passive+no_connect"))
    )
    (net (code "72") (name "unconnected-(U12-BCLK_OUT3-Pad51)") (class "Default")
      (node (ref "U12") (pin "51") (pinfunction "BCLK_OUT3_51") (pintype "passive+no_connect"))
    )
    (net (code "73") (name "unconnected-(U12-CLKOUT-Pad23)") (class "Default")
      (node (ref "U12") (pin "23") (pinfunction "CLKOUT_23") (pintype "passive+no_connect"))
    )
    (net (code "74") (name "unconnected-(U12-LRCLK_IN3{slash}MP13-Pad69)") (class "Default")
      (node (ref "U12") (pin "69") (pinfunction "LRCLK_IN3/MP13_69") (pintype "passive+no_connect"))
    )
    (net (code "75") (name "unconnected-(U12-SDATA_IN3-Pad70)") (class "Default")
      (node (ref "U12") (pin "70") (pinfunction "SDATA_IN3_70") (pintype "passive+no_connect"))
    )
    (net (code "76") (name "unconnected-(U12-SDATA_OUT2-Pad49)") (class "Default")
      (node (ref "U12") (pin "49") (pinfunction "SDATA_OUT2_49") (pintype "passive+no_connect"))
    )
    (net (code "77") (name "unconnected-(U12-SDATA_OUT3-Pad52)") (class "Default")
      (node (ref "U12") (pin "52") (pinfunction "SDATA_OUT3_52") (pintype "passive+no_connect"))
    )
    (net (code "78") (name "unconnected-(U12-SPDIFIN-Pad4)") (class "Default")
      (node (ref "U12") (pin "4") (pinfunction "SPDIFIN_4") (pintype "passive+no_connect"))
    )
    (net (code "79") (name "unconnected-(U12-SPDIFOUT-Pad5)") (class "Default")
      (node (ref "U12") (pin "5") (pinfunction "SPDIFOUT_5") (pintype "passive+no_connect"))
    )
    (net (code "80") (name "unconnected-(U12-THD_M-Pad63)") (class "Default")
      (node (ref "U12") (pin "63") (pinfunction "THD_M_63") (pintype "passive+no_connect"))
    )
    (net (code "81") (name "unconnected-(U12-THD_P-Pad64)") (class "Default")
      (node (ref "U12") (pin "64") (pinfunction "THD_P_64") (pintype "passive+no_connect"))
    )
    (net (code "82") (name "unconnected-(U12-XTALOUT-Pad22)") (class "Default")
      (node (ref "U12") (pin "22") (pinfunction "XTALOUT_22") (pintype "passive+no_connect"))
    )
  )
)
